# LW_upconverter.net
KiCad netlist of a schematic drawn in EAGLE
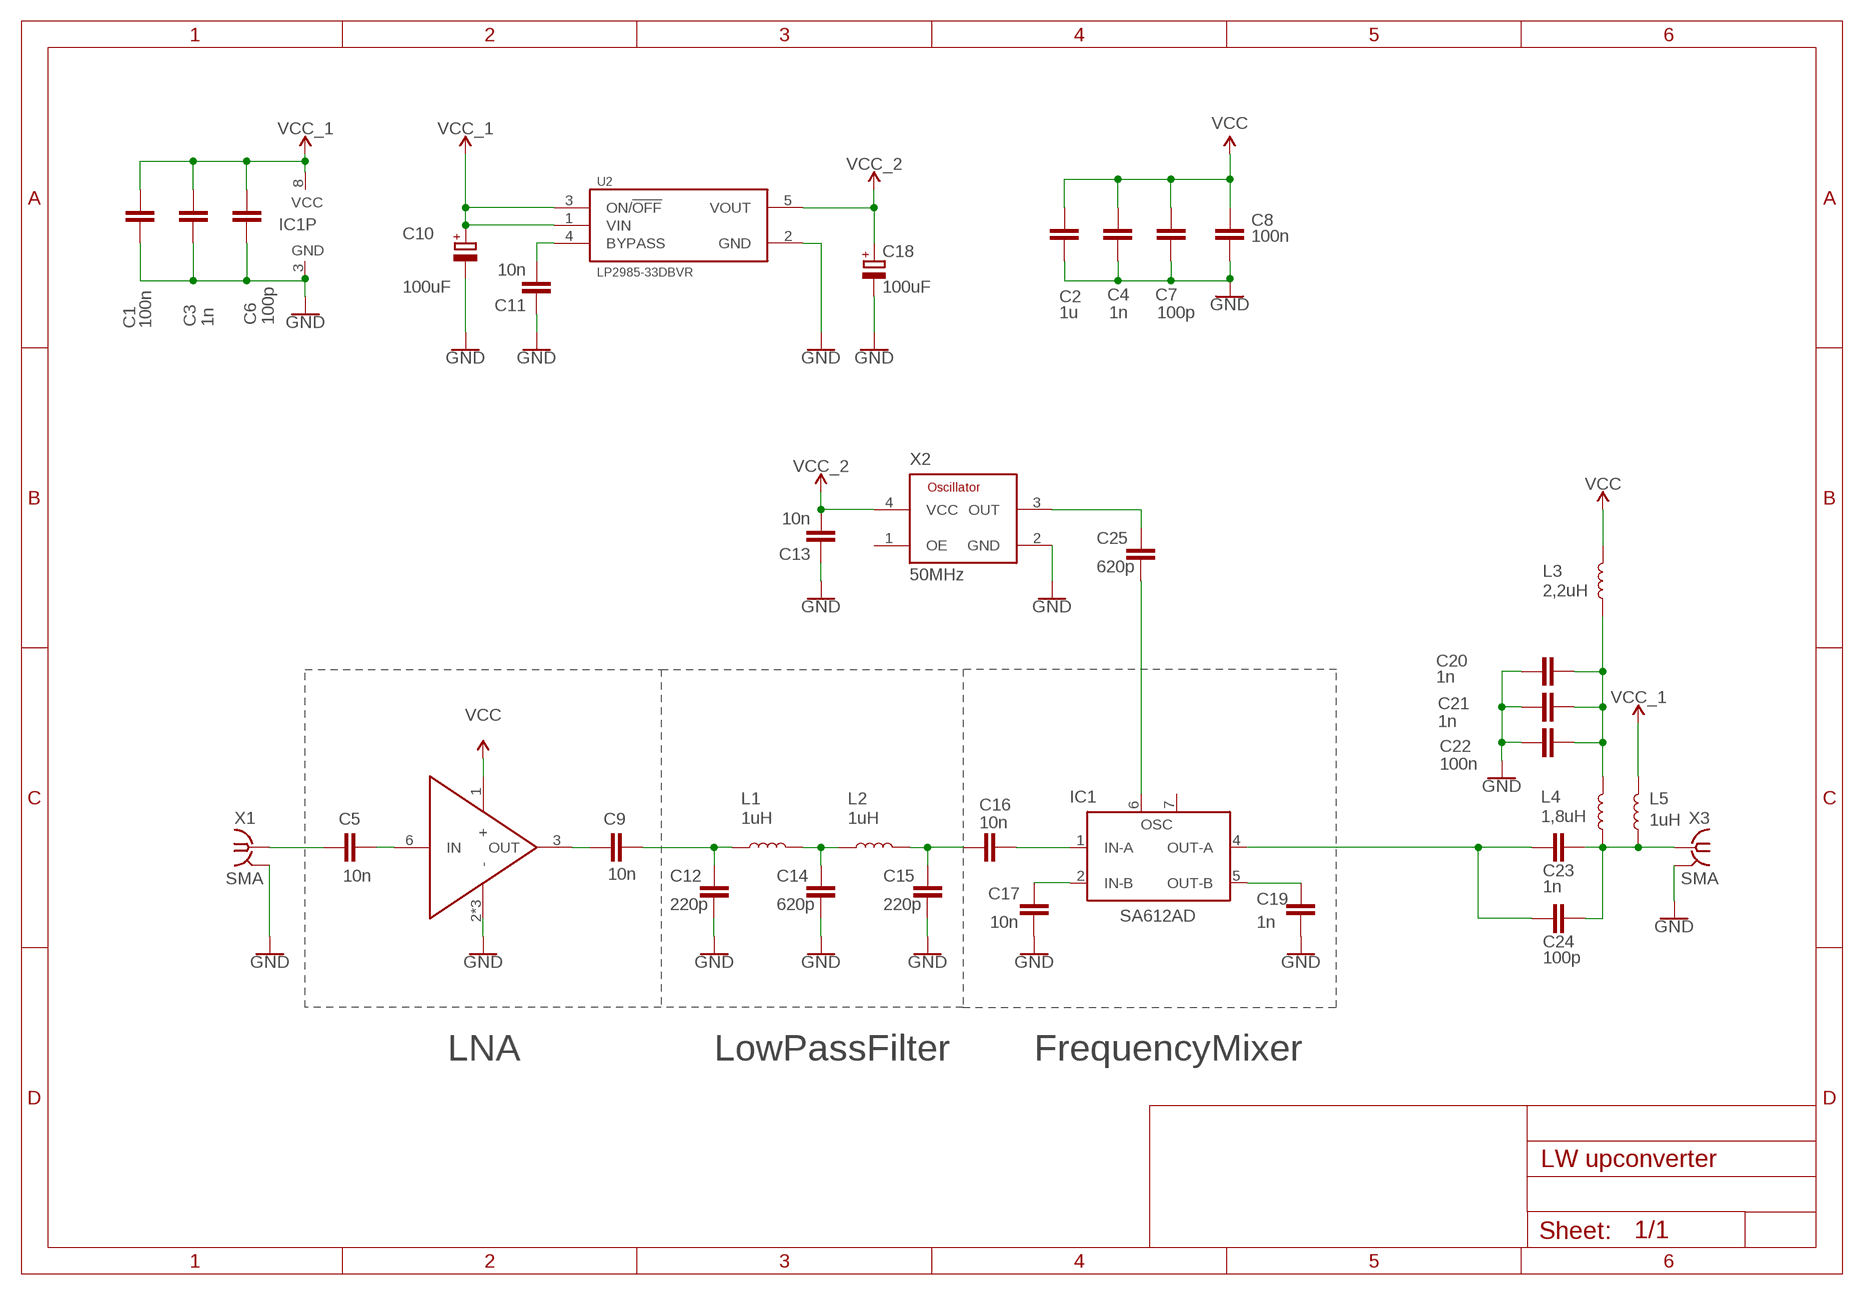
[diagram p0: schematic, sheet 1]

(export (version "E")
  (design (tool "Eeschema 10.0.6"))
  (components
    (comp (ref "C1")
      (value "100n")
      (footprint "eagle-import:C0603K")
      (libsource (lib "eagle-import") (part "C-EUC0603K"))
    )
    (comp (ref "C2")
      (value "1u")
      (footprint "eagle-import:C0603K")
      (libsource (lib "eagle-import") (part "C-EUC0603K"))
    )
    (comp (ref "C3")
      (value "1n")
      (footprint "eagle-import:C0603K")
      (libsource (lib "eagle-import") (part "C-EUC0603K"))
    )
    (comp (ref "C4")
      (value "1n")
      (footprint "eagle-import:C0603K")
      (libsource (lib "eagle-import") (part "C-EUC0603K"))
    )
    (comp (ref "C5")
      (value "10n")
      (footprint "eagle-import:C0603K")
      (libsource (lib "eagle-import") (part "C-EUC0603K"))
    )
    (comp (ref "C6")
      (value "100p")
      (footprint "eagle-import:C0603K")
      (libsource (lib "eagle-import") (part "C-EUC0603K"))
    )
    (comp (ref "C7")
      (value "100p")
      (footprint "eagle-import:C0603K")
      (libsource (lib "eagle-import") (part "C-EUC0603K"))
    )
    (comp (ref "C8")
      (value "100n")
      (footprint "eagle-import:C0603K")
      (libsource (lib "eagle-import") (part "C-EUC0603K"))
    )
    (comp (ref "C9")
      (value "10n")
      (footprint "eagle-import:C0603K")
      (libsource (lib "eagle-import") (part "C-EUC0603K"))
    )
    (comp (ref "C10")
      (value "100uF")
      (footprint "eagle-import:CT3528")
      (libsource (lib "eagle-import") (part "CPOL-EUCT3528"))
    )
    (comp (ref "C11")
      (value "10n")
      (footprint "eagle-import:C0603K")
      (libsource (lib "eagle-import") (part "C-EUC0603K"))
    )
    (comp (ref "C12")
      (value "220p")
      (footprint "eagle-import:C0603K")
      (libsource (lib "eagle-import") (part "C-EUC0603K"))
    )
    (comp (ref "C13")
      (value "10n")
      (footprint "eagle-import:C0603K")
      (libsource (lib "eagle-import") (part "C-EUC0603K"))
    )
    (comp (ref "C14")
      (value "620p")
      (footprint "eagle-import:C0603K")
      (libsource (lib "eagle-import") (part "C-EUC0603K"))
    )
    (comp (ref "C15")
      (value "220p")
      (footprint "eagle-import:C0603K")
      (libsource (lib "eagle-import") (part "C-EUC0603K"))
    )
    (comp (ref "C16")
      (value "10n")
      (footprint "eagle-import:C0603K")
      (libsource (lib "eagle-import") (part "C-EUC0603K"))
    )
    (comp (ref "C17")
      (value "10n")
      (footprint "eagle-import:C0603K")
      (libsource (lib "eagle-import") (part "C-EUC0603K"))
    )
    (comp (ref "C18")
      (value "100uF")
      (footprint "eagle-import:CT3528")
      (libsource (lib "eagle-import") (part "CPOL-EUCT3528"))
    )
    (comp (ref "C19")
      (value "1n")
      (footprint "eagle-import:C0603K")
      (libsource (lib "eagle-import") (part "C-EUC0603K"))
    )
    (comp (ref "C20")
      (value "1n")
      (footprint "eagle-import:C0603K")
      (libsource (lib "eagle-import") (part "C-EUC0603K"))
    )
    (comp (ref "C21")
      (value "1n")
      (footprint "eagle-import:C0603K")
      (libsource (lib "eagle-import") (part "C-EUC0603K"))
    )
    (comp (ref "C22")
      (value "100n")
      (footprint "eagle-import:C0603K")
      (libsource (lib "eagle-import") (part "C-EUC0603K"))
    )
    (comp (ref "C23")
      (value "1n")
      (footprint "eagle-import:C0603K")
      (libsource (lib "eagle-import") (part "C-EUC0603K"))
    )
    (comp (ref "C24")
      (value "100p")
      (footprint "eagle-import:C0603K")
      (libsource (lib "eagle-import") (part "C-EUC0603K"))
    )
    (comp (ref "C25")
      (value "620p")
      (footprint "eagle-import:C0603K")
      (libsource (lib "eagle-import") (part "C-EUC0603K"))
    )
    (comp (ref "IC1")
      (value "SA612AD")
      (footprint "eagle-import:SO08")
      (libsource (lib "eagle-import") (part "SA612AD"))
    )
    (comp (ref "L1")
      (value "1uH")
      (footprint "eagle-import:0603")
      (libsource (lib "eagle-import") (part "INDUCTOR-0603-33NH"))
    )
    (comp (ref "L2")
      (value "1uH")
      (footprint "eagle-import:0603")
      (libsource (lib "eagle-import") (part "INDUCTOR-0603-33NH"))
    )
    (comp (ref "L3")
      (value "2,2uH")
      (footprint "eagle-import:0603")
      (libsource (lib "eagle-import") (part "INDUCTOR-0603-33NH"))
    )
    (comp (ref "L4")
      (value "1,8uH")
      (footprint "eagle-import:0603")
      (libsource (lib "eagle-import") (part "INDUCTOR-0603-33NH"))
    )
    (comp (ref "L5")
      (value "1uH")
      (footprint "eagle-import:0603")
      (libsource (lib "eagle-import") (part "INDUCTOR-0603-33NH"))
    )
    (comp (ref "U1")
      (value "BGA28XX_BGA28XX")
      (footprint "eagle-import:BGA28XX_SOT363_PHILIPS")
      (libsource (lib "eagle-import") (part "BGA28XX_BGA28XX"))
    )
    (comp (ref "U2")
      (value "LP2985-33DBVR")
      (footprint "eagle-import:SOT95P280X145-5N")
      (fields (field (name "MF") "Texas Instruments"))
      (libsource (lib "eagle-import") (part "LP2985-33DBVR"))
    )
    (comp (ref "X1")
      (value "SMA")
      (footprint "eagle-import:J502-ND-142-0711-881_886")
      (fields (field (name "MF") "JOHNSON COMPONENTS") (field (name "MPN") "142-0711-881"))
      (libsource (lib "eagle-import") (part "SMA-142-0711-881/886"))
    )
    (comp (ref "X2")
      (value "50MHz")
      (footprint "eagle-import:ASF1_ASFL_ASFL1")
      (libsource (lib "eagle-import") (part "OSCILLATORS-1"))
    )
    (comp (ref "X3")
      (value "SMA")
      (footprint "eagle-import:J502-ND-142-0711-881_886")
      (fields (field (name "MF") "JOHNSON COMPONENTS") (field (name "MPN") "142-0711-881"))
      (libsource (lib "eagle-import") (part "SMA-142-0711-881/886"))
    )
  )
  (nets
    (net (code "1") (name "GND") (class "Default")
      (node (ref "C1") (pin "2") (pinfunction "2_2") (pintype "passive"))
      (node (ref "C10") (pin "-") (pinfunction "-_-") (pintype "passive"))
      (node (ref "C11") (pin "1") (pinfunction "1_1") (pintype "passive"))
      (node (ref "C12") (pin "1") (pinfunction "1_1") (pintype "passive"))
      (node (ref "C13") (pin "1") (pinfunction "1_1") (pintype "passive"))
      (node (ref "C14") (pin "1") (pinfunction "1_1") (pintype "passive"))
      (node (ref "C15") (pin "1") (pinfunction "1_1") (pintype "passive"))
      (node (ref "C17") (pin "1") (pinfunction "1_1") (pintype "passive"))
      (node (ref "C18") (pin "-") (pinfunction "-_-") (pintype "passive"))
      (node (ref "C19") (pin "1") (pinfunction "1_1") (pintype "passive"))
      (node (ref "C2") (pin "2") (pinfunction "2_2") (pintype "passive"))
      (node (ref "C20") (pin "2") (pinfunction "2_2") (pintype "passive"))
      (node (ref "C21") (pin "2") (pinfunction "2_2") (pintype "passive"))
      (node (ref "C22") (pin "2") (pinfunction "2_2") (pintype "passive"))
      (node (ref "C3") (pin "2") (pinfunction "2_2") (pintype "passive"))
      (node (ref "C4") (pin "2") (pinfunction "2_2") (pintype "passive"))
      (node (ref "C6") (pin "2") (pinfunction "2_2") (pintype "passive"))
      (node (ref "C7") (pin "2") (pinfunction "2_2") (pintype "passive"))
      (node (ref "C8") (pin "1") (pinfunction "1_1") (pintype "passive"))
      (node (ref "IC1") (pin "3") (pinfunction "GND_3") (pintype "power_in"))
      (node (ref "U1") (pin "2") (pinfunction "-_2") (pintype "bidirectional"))
      (node (ref "U1") (pin "4") (pinfunction "-_4") (pintype "bidirectional"))
      (node (ref "U1") (pin "5") (pinfunction "-_5") (pintype "bidirectional"))
      (node (ref "U2") (pin "2") (pinfunction "GND_2") (pintype "power_in"))
      (node (ref "X1") (pin "G@1") (pinfunction "2_G@1") (pintype "passive"))
      (node (ref "X1") (pin "G@2") (pinfunction "2_G@2") (pintype "passive"))
      (node (ref "X1") (pin "G@3") (pinfunction "2_G@3") (pintype "passive"))
      (node (ref "X1") (pin "G@4") (pinfunction "2_G@4") (pintype "passive"))
      (node (ref "X2") (pin "2") (pinfunction "GND_2") (pintype "power_in"))
      (node (ref "X3") (pin "G@1") (pinfunction "2_G@1") (pintype "passive"))
      (node (ref "X3") (pin "G@2") (pinfunction "2_G@2") (pintype "passive"))
      (node (ref "X3") (pin "G@3") (pinfunction "2_G@3") (pintype "passive"))
      (node (ref "X3") (pin "G@4") (pinfunction "2_G@4") (pintype "passive"))
    )
    (net (code "2") (name "Net-(C5-Pad1)") (class "Default")
      (node (ref "C5") (pin "1") (pinfunction "1_1") (pintype "passive"))
      (node (ref "X1") (pin "1") (pinfunction "1_1") (pintype "passive"))
    )
    (net (code "3") (name "Net-(C12-Pad2)") (class "Default")
      (node (ref "C12") (pin "2") (pinfunction "2_2") (pintype "passive"))
      (node (ref "C9") (pin "2") (pinfunction "2_2") (pintype "passive"))
      (node (ref "L1") (pin "1") (pinfunction "1_1") (pintype "passive"))
    )
    (net (code "4") (name "Net-(C14-Pad2)") (class "Default")
      (node (ref "C14") (pin "2") (pinfunction "2_2") (pintype "passive"))
      (node (ref "L1") (pin "2") (pinfunction "2_2") (pintype "passive"))
      (node (ref "L2") (pin "1") (pinfunction "1_1") (pintype "passive"))
    )
    (net (code "5") (name "Net-(C15-Pad2)") (class "Default")
      (node (ref "C15") (pin "2") (pinfunction "2_2") (pintype "passive"))
      (node (ref "C16") (pin "2") (pinfunction "2_2") (pintype "passive"))
      (node (ref "L2") (pin "2") (pinfunction "2_2") (pintype "passive"))
    )
    (net (code "6") (name "Net-(C20-Pad1)") (class "Default")
      (node (ref "C20") (pin "1") (pinfunction "1_1") (pintype "passive"))
      (node (ref "C21") (pin "1") (pinfunction "1_1") (pintype "passive"))
      (node (ref "C22") (pin "1") (pinfunction "1_1") (pintype "passive"))
      (node (ref "L3") (pin "1") (pinfunction "1_1") (pintype "passive"))
      (node (ref "L4") (pin "2") (pinfunction "2_2") (pintype "passive"))
    )
    (net (code "7") (name "Net-(C23-Pad1)") (class "Default")
      (node (ref "C23") (pin "1") (pinfunction "1_1") (pintype "passive"))
      (node (ref "C24") (pin "1") (pinfunction "1_1") (pintype "passive"))
      (node (ref "L4") (pin "1") (pinfunction "1_1") (pintype "passive"))
      (node (ref "L5") (pin "1") (pinfunction "1_1") (pintype "passive"))
      (node (ref "X3") (pin "1") (pinfunction "1_1") (pintype "passive"))
    )
    (net (code "8") (name "Net-(IC1A-IN-A)") (class "Default")
      (node (ref "C16") (pin "1") (pinfunction "1_1") (pintype "passive"))
      (node (ref "IC1") (pin "1") (pinfunction "IN-A_1") (pintype "input"))
    )
    (net (code "9") (name "Net-(IC1A-IN-B)") (class "Default")
      (node (ref "C17") (pin "2") (pinfunction "2_2") (pintype "passive"))
      (node (ref "IC1") (pin "2") (pinfunction "IN-B_2") (pintype "input"))
    )
    (net (code "10") (name "Net-(IC1A-OSC)") (class "Default")
      (node (ref "C25") (pin "1") (pinfunction "1_1") (pintype "passive"))
      (node (ref "IC1") (pin "6") (pinfunction "OSC_6") (pintype "passive"))
    )
    (net (code "11") (name "Net-(IC1A-OUT-A)") (class "Default")
      (node (ref "C23") (pin "2") (pinfunction "2_2") (pintype "passive"))
      (node (ref "C24") (pin "2") (pinfunction "2_2") (pintype "passive"))
      (node (ref "IC1") (pin "4") (pinfunction "OUT-A_4") (pintype "input"))
    )
    (net (code "12") (name "Net-(IC1A-OUT-B)") (class "Default")
      (node (ref "C19") (pin "2") (pinfunction "2_2") (pintype "passive"))
      (node (ref "IC1") (pin "5") (pinfunction "OUT-B_5") (pintype "input"))
    )
    (net (code "13") (name "Net-(U1-IN)") (class "Default")
      (node (ref "C5") (pin "2") (pinfunction "2_2") (pintype "passive"))
      (node (ref "U1") (pin "6") (pinfunction "IN_6") (pintype "bidirectional"))
    )
    (net (code "14") (name "Net-(U1-OUT)") (class "Default")
      (node (ref "C9") (pin "1") (pinfunction "1_1") (pintype "passive"))
      (node (ref "U1") (pin "3") (pinfunction "OUT_3") (pintype "bidirectional"))
    )
    (net (code "15") (name "Net-(U2-BYPASS)") (class "Default")
      (node (ref "C11") (pin "2") (pinfunction "2_2") (pintype "passive"))
      (node (ref "U2") (pin "4") (pinfunction "BYPASS_4") (pintype "bidirectional"))
    )
    (net (code "16") (name "Net-(X2-OUT)") (class "Default")
      (node (ref "C25") (pin "2") (pinfunction "2_2") (pintype "passive"))
      (node (ref "X2") (pin "3") (pinfunction "OUT_3") (pintype "output"))
    )
    (net (code "17") (name "VCC") (class "Default")
      (node (ref "C2") (pin "1") (pinfunction "1_1") (pintype "passive"))
      (node (ref "C4") (pin "1") (pinfunction "1_1") (pintype "passive"))
      (node (ref "C7") (pin "1") (pinfunction "1_1") (pintype "passive"))
      (node (ref "C8") (pin "2") (pinfunction "2_2") (pintype "passive"))
      (node (ref "L3") (pin "2") (pinfunction "2_2") (pintype "passive"))
      (node (ref "U1") (pin "1") (pinfunction "+_1") (pintype "bidirectional"))
    )
    (net (code "18") (name "VCC_1") (class "Default")
      (node (ref "C1") (pin "1") (pinfunction "1_1") (pintype "passive"))
      (node (ref "C10") (pin "+") (pinfunction "+_+") (pintype "passive"))
      (node (ref "C3") (pin "1") (pinfunction "1_1") (pintype "passive"))
      (node (ref "C6") (pin "1") (pinfunction "1_1") (pintype "passive"))
      (node (ref "IC1") (pin "8") (pinfunction "VCC_8") (pintype "power_in"))
      (node (ref "L5") (pin "2") (pinfunction "2_2") (pintype "passive"))
      (node (ref "U2") (pin "1") (pinfunction "VIN_1") (pintype "input"))
      (node (ref "U2") (pin "3") (pinfunction "ON/~{OFF}_3") (pintype "input"))
    )
    (net (code "19") (name "VCC_2") (class "Default")
      (node (ref "C13") (pin "2") (pinfunction "2_2") (pintype "passive"))
      (node (ref "C18") (pin "+") (pinfunction "+_+") (pintype "passive"))
      (node (ref "U2") (pin "5") (pinfunction "VOUT_5") (pintype "output"))
      (node (ref "X2") (pin "4") (pinfunction "VCC_4") (pintype "power_in"))
    )
    (net (code "20") (name "unconnected-(IC1A-OSC'-Pad7)") (class "Default")
      (node (ref "IC1") (pin "7") (pinfunction "OSC'_7") (pintype "passive"))
    )
    (net (code "21") (name "unconnected-(X2-OE-Pad1)") (class "Default")
      (node (ref "X2") (pin "1") (pinfunction "OE_1") (pintype "input"))
    )
  )
)
